# EagleSchematicv4.net
KiCad netlist of a schematic drawn in EAGLE
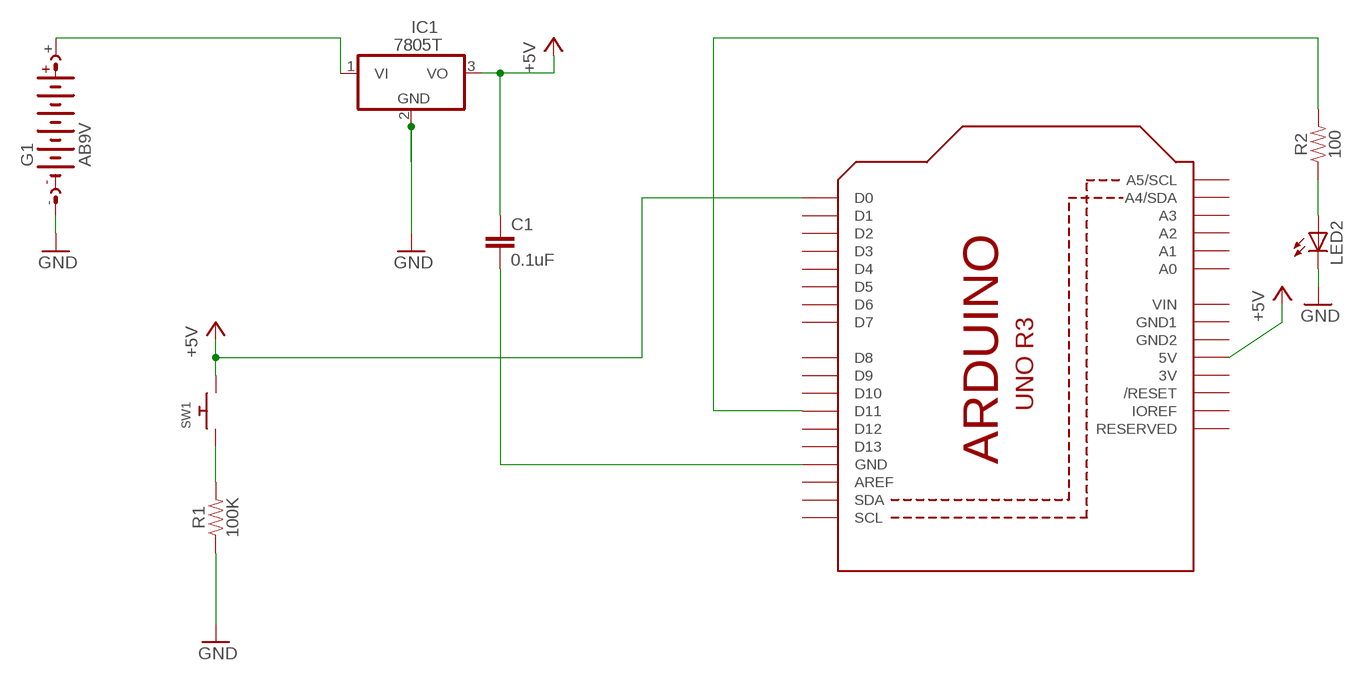
[diagram p0: schematic, sheet 1]

(export (version "E")
  (design (tool "Eeschema 10.0.6"))
  (components
    (comp (ref "C1")
      (value "0.1uF")
      (footprint "eagle-import:0402")
      (libsource (lib "eagle-import") (part "0.1UF-0402-16V-10%"))
    )
    (comp (ref "G1")
      (value "AB9V")
      (footprint "eagle-import:AB9V")
      (libsource (lib "eagle-import") (part "AB9V"))
    )
    (comp (ref "IC1")
      (value "7805T")
      (footprint "eagle-import:TO220H")
      (libsource (lib "eagle-import") (part "78T05"))
    )
    (comp (ref "LED2")
      (value "LED5MM")
      (footprint "eagle-import:LED5MM")
      (libsource (lib "eagle-import") (part "LED5MM"))
    )
    (comp (ref "R1")
      (value "100K")
      (footprint "eagle-import:0402")
      (libsource (lib "eagle-import") (part "100KOHM-0402-1/16W-1%"))
    )
    (comp (ref "R2")
      (value "100")
      (footprint "eagle-import:0603")
      (libsource (lib "eagle-import") (part "100OHM-0603-1/4W-5%"))
    )
    (comp (ref "SW1")
      (value "SWITCH_PUSHBUTTONSOFTTOUCHSMD_SJ")
      (footprint "eagle-import:PUSHBUTTON_SMD_SJ")
      (libsource (lib "eagle-import") (part "SWITCH_PUSHBUTTONSOFTTOUCHSMD_SJ"))
    )
    (comp (ref "U1")
      (value "ARDUINOR3-BPLACE")
      (footprint "eagle-import:ARDUINOR3-BPLACE")
      (libsource (lib "eagle-import") (part "ARDUINOR3-BPLACE"))
    )
  )
  (nets
    (net (code "1") (name "+5V") (class "Default")
      (node (ref "C1") (pin "1") (pinfunction "1_1") (pintype "passive"))
      (node (ref "IC1") (pin "3") (pinfunction "VO_3") (pintype "passive"))
      (node (ref "SW1") (pin "P$2") (pinfunction "P$2_P$2") (pintype "passive"))
      (node (ref "U1") (pin "5V") (pinfunction "5V_5V") (pintype "power_in"))
      (node (ref "U1") (pin "D0") (pinfunction "D0_D0") (pintype "bidirectional"))
    )
    (net (code "2") (name "/3V") (class "Default")
      (node (ref "U1") (pin "3V") (pinfunction "3V_3V") (pintype "power_in"))
    )
    (net (code "3") (name "/GND1") (class "Default")
      (node (ref "U1") (pin "GND1") (pinfunction "GND1_GND1") (pintype "power_in"))
    )
    (net (code "4") (name "/GND2") (class "Default")
      (node (ref "U1") (pin "GND2") (pinfunction "GND2_GND2") (pintype "power_in"))
    )
    (net (code "5") (name "/VIN") (class "Default")
      (node (ref "U1") (pin "VIN") (pinfunction "VIN_VIN") (pintype "power_in"))
    )
    (net (code "6") (name "GND") (class "Default")
      (node (ref "G1") (pin "-") (pinfunction "-_-") (pintype "passive"))
      (node (ref "IC1") (pin "2") (pinfunction "GND_2") (pintype "passive"))
      (node (ref "LED2") (pin "K") (pinfunction "C_K") (pintype "passive"))
      (node (ref "R1") (pin "1") (pinfunction "1_1") (pintype "passive"))
    )
    (net (code "7") (name "Net-(C1-Pad2)") (class "Default")
      (node (ref "C1") (pin "2") (pinfunction "2_2") (pintype "passive"))
      (node (ref "U1") (pin "GND") (pinfunction "GND_GND") (pintype "power_in"))
    )
    (net (code "8") (name "Net-(IC1-VI)") (class "Default")
      (node (ref "G1") (pin "+") (pinfunction "+_+") (pintype "passive"))
      (node (ref "IC1") (pin "1") (pinfunction "VI_1") (pintype "input"))
    )
    (net (code "9") (name "Net-(LED2-PadA)") (class "Default")
      (node (ref "LED2") (pin "A") (pinfunction "A_A") (pintype "passive"))
      (node (ref "R2") (pin "1") (pinfunction "1_1") (pintype "passive"))
    )
    (net (code "10") (name "Net-(R1-Pad2)") (class "Default")
      (node (ref "R1") (pin "2") (pinfunction "2_2") (pintype "passive"))
      (node (ref "SW1") (pin "P$1") (pinfunction "P$1_P$1") (pintype "passive"))
    )
    (net (code "11") (name "Net-(R2-Pad2)") (class "Default")
      (node (ref "R2") (pin "2") (pinfunction "2_2") (pintype "passive"))
      (node (ref "U1") (pin "D11") (pinfunction "D11_D11") (pintype "bidirectional"))
    )
    (net (code "12") (name "unconnected-(U1-A4{slash}SDA-PadA4)") (class "Default")
      (node (ref "U1") (pin "A4") (pinfunction "A4/SDA_A4") (pintype "bidirectional"))
    )
    (net (code "13") (name "unconnected-(U1-A5{slash}SCL-PadA5)") (class "Default")
      (node (ref "U1") (pin "A5") (pinfunction "A5/SCL_A5") (pintype "bidirectional"))
    )
    (net (code "14") (name "unconnected-(U1-PadA0)") (class "Default")
      (node (ref "U1") (pin "A0") (pinfunction "A0_A0") (pintype "bidirectional"))
    )
    (net (code "15") (name "unconnected-(U1-PadA1)") (class "Default")
      (node (ref "U1") (pin "A1") (pinfunction "A1_A1") (pintype "bidirectional"))
    )
    (net (code "16") (name "unconnected-(U1-PadA2)") (class "Default")
      (node (ref "U1") (pin "A2") (pinfunction "A2_A2") (pintype "bidirectional"))
    )
    (net (code "17") (name "unconnected-(U1-PadA3)") (class "Default")
      (node (ref "U1") (pin "A3") (pinfunction "A3_A3") (pintype "bidirectional"))
    )
    (net (code "18") (name "unconnected-(U1-PadAREF)") (class "Default")
      (node (ref "U1") (pin "AREF") (pinfunction "AREF_AREF") (pintype "bidirectional"))
    )
    (net (code "19") (name "unconnected-(U1-PadD1)") (class "Default")
      (node (ref "U1") (pin "D1") (pinfunction "D1_D1") (pintype "bidirectional"))
    )
    (net (code "20") (name "unconnected-(U1-PadD2)") (class "Default")
      (node (ref "U1") (pin "D2") (pinfunction "D2_D2") (pintype "bidirectional"))
    )
    (net (code "21") (name "unconnected-(U1-PadD3)") (class "Default")
      (node (ref "U1") (pin "D3") (pinfunction "D3_D3") (pintype "bidirectional"))
    )
    (net (code "22") (name "unconnected-(U1-PadD4)") (class "Default")
      (node (ref "U1") (pin "D4") (pinfunction "D4_D4") (pintype "bidirectional"))
    )
    (net (code "23") (name "unconnected-(U1-PadD5)") (class "Default")
      (node (ref "U1") (pin "D5") (pinfunction "D5_D5") (pintype "bidirectional"))
    )
    (net (code "24") (name "unconnected-(U1-PadD6)") (class "Default")
      (node (ref "U1") (pin "D6") (pinfunction "D6_D6") (pintype "bidirectional"))
    )
    (net (code "25") (name "unconnected-(U1-PadD7)") (class "Default")
      (node (ref "U1") (pin "D7") (pinfunction "D7_D7") (pintype "bidirectional"))
    )
    (net (code "26") (name "unconnected-(U1-PadD8)") (class "Default")
      (node (ref "U1") (pin "D8") (pinfunction "D8_D8") (pintype "bidirectional"))
    )
    (net (code "27") (name "unconnected-(U1-PadD9)") (class "Default")
      (node (ref "U1") (pin "D9") (pinfunction "D9_D9") (pintype "bidirectional"))
    )
    (net (code "28") (name "unconnected-(U1-PadD10)") (class "Default")
      (node (ref "U1") (pin "D10") (pinfunction "D10_D10") (pintype "bidirectional"))
    )
    (net (code "29") (name "unconnected-(U1-PadD12)") (class "Default")
      (node (ref "U1") (pin "D12") (pinfunction "D12_D12") (pintype "bidirectional"))
    )
    (net (code "30") (name "unconnected-(U1-PadD13)") (class "Default")
      (node (ref "U1") (pin "D13") (pinfunction "D13_D13") (pintype "bidirectional"))
    )
    (net (code "31") (name "unconnected-(U1-PadIOREF)") (class "Default")
      (node (ref "U1") (pin "IOREF") (pinfunction "IOREF_IOREF") (pintype "output"))
    )
    (net (code "32") (name "unconnected-(U1-PadRESERVED)") (class "Default")
      (node (ref "U1") (pin "RESERVED") (pinfunction "RESERVED_RESERVED") (pintype "no_connect"))
    )
    (net (code "33") (name "unconnected-(U1-PadSCL)") (class "Default")
      (node (ref "U1") (pin "SCL") (pinfunction "SCL_SCL") (pintype "bidirectional"))
    )
    (net (code "34") (name "unconnected-(U1-PadSDA)") (class "Default")
      (node (ref "U1") (pin "SDA") (pinfunction "SDA_SDA") (pintype "bidirectional"))
    )
    (net (code "35") (name "unconnected-(U1-{slash}RESET-PadRESET)") (class "Default")
      (node (ref "U1") (pin "RESET") (pinfunction "/RESET_RESET") (pintype "bidirectional"))
    )
  )
)
